# proiect.net
KiCad netlist of a schematic drawn in EAGLE
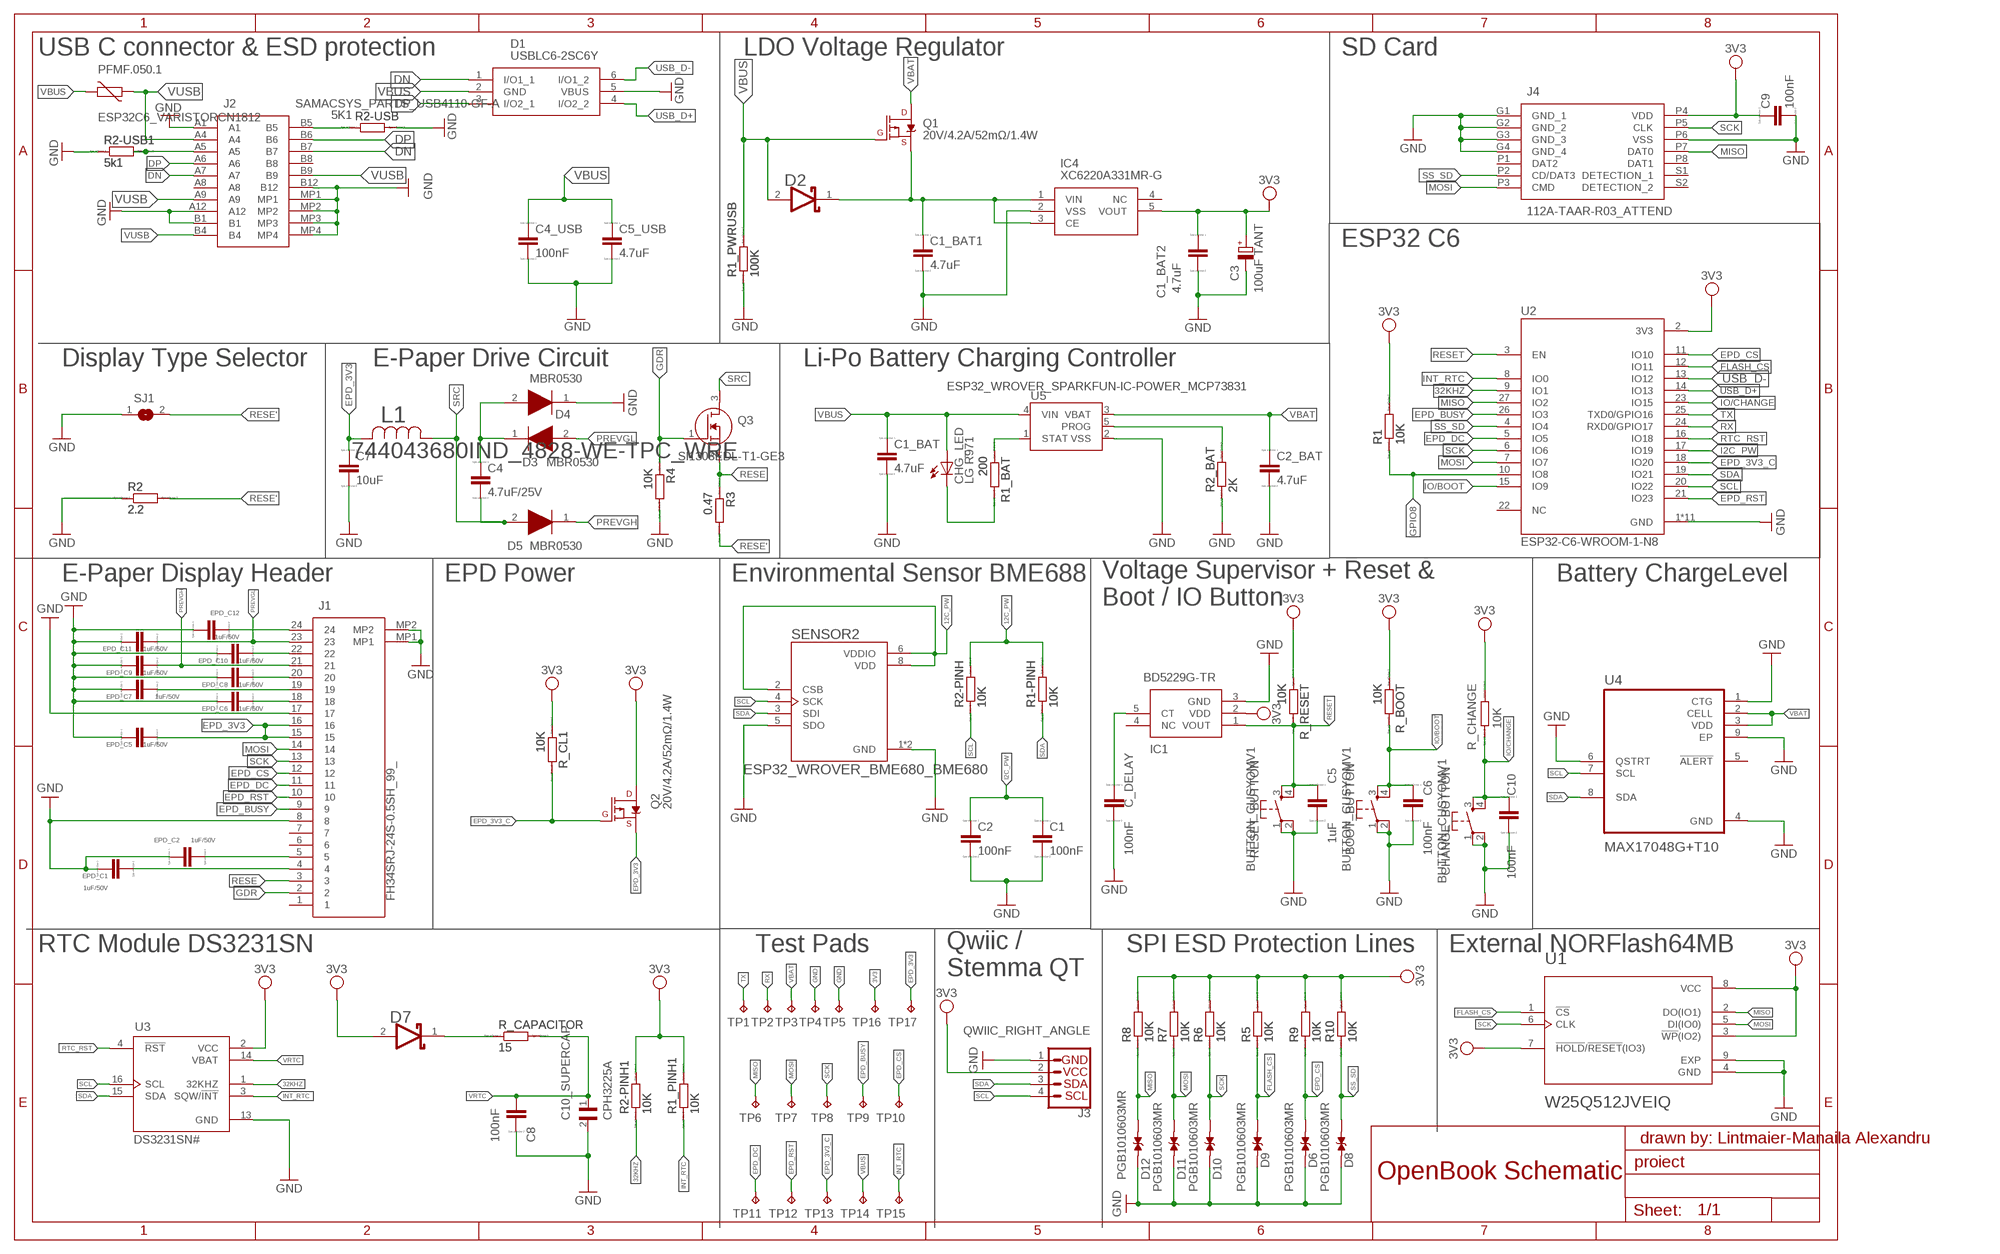
[diagram p0: schematic, sheet 1]

(export (version "E")
  (design (tool "Eeschema 10.0.6"))
  (components
    (comp (ref "BOOT_BUTTON")
      (value "BUTTON_CUSYOMV1")
      (footprint "eagle-import:MYBUTTON")
      (libsource (lib "eagle-import") (part "BUTTON_CUSYOMV1"))
    )
    (comp (ref "C1")
      (value "100nF")
      (footprint "eagle-import:EAGLE-LTSPICE_C0402")
      (libsource (lib "eagle-import") (part "EAGLE-LTSPICE_CC0402"))
    )
    (comp (ref "C1_BAT")
      (value "4.7uF")
      (footprint "eagle-import:EAGLE-LTSPICE_C0402")
      (libsource (lib "eagle-import") (part "EAGLE-LTSPICE_CC0402"))
    )
    (comp (ref "C1_BAT1")
      (value "4.7uF")
      (footprint "eagle-import:EAGLE-LTSPICE_C0402")
      (libsource (lib "eagle-import") (part "EAGLE-LTSPICE_CC0402"))
    )
    (comp (ref "C1_BAT2")
      (value "4.7uF")
      (footprint "eagle-import:EAGLE-LTSPICE_C0402")
      (libsource (lib "eagle-import") (part "EAGLE-LTSPICE_CC0402"))
    )
    (comp (ref "C2")
      (value "100nF")
      (footprint "eagle-import:EAGLE-LTSPICE_C0402")
      (libsource (lib "eagle-import") (part "EAGLE-LTSPICE_CC0402"))
    )
    (comp (ref "C2_BAT")
      (value "4.7uF")
      (footprint "eagle-import:EAGLE-LTSPICE_C0402")
      (libsource (lib "eagle-import") (part "EAGLE-LTSPICE_CC0402"))
    )
    (comp (ref "C3")
      (value "100uF TANT")
      (footprint "eagle-import:RCL_CT3528")
      (libsource (lib "eagle-import") (part "RCL_CPOL-EUCT3528"))
    )
    (comp (ref "C4")
      (value "4.7uF/25V")
      (footprint "eagle-import:EAGLE-LTSPICE_C0402")
      (libsource (lib "eagle-import") (part "EAGLE-LTSPICE_CC0402"))
    )
    (comp (ref "C4_USB")
      (value "100nF")
      (footprint "eagle-import:EAGLE-LTSPICE_C0402")
      (libsource (lib "eagle-import") (part "EAGLE-LTSPICE_CC0402"))
    )
    (comp (ref "C5")
      (value "1uF")
      (footprint "eagle-import:EAGLE-LTSPICE_C0402")
      (libsource (lib "eagle-import") (part "EAGLE-LTSPICE_CC0402"))
    )
    (comp (ref "C5_USB")
      (value "4.7uF")
      (footprint "eagle-import:EAGLE-LTSPICE_C0402")
      (libsource (lib "eagle-import") (part "EAGLE-LTSPICE_CC0402"))
    )
    (comp (ref "C6")
      (value "100nF")
      (footprint "eagle-import:EAGLE-LTSPICE_C0402")
      (libsource (lib "eagle-import") (part "EAGLE-LTSPICE_CC0402"))
    )
    (comp (ref "C7")
      (value "10uF")
      (footprint "eagle-import:EAGLE-LTSPICE_C0402")
      (libsource (lib "eagle-import") (part "EAGLE-LTSPICE_CC0402"))
    )
    (comp (ref "C8")
      (value "100nF")
      (footprint "eagle-import:EAGLE-LTSPICE_C0402")
      (libsource (lib "eagle-import") (part "EAGLE-LTSPICE_CC0402"))
    )
    (comp (ref "C9")
      (value "100nF")
      (footprint "eagle-import:EAGLE-LTSPICE_C0402")
      (libsource (lib "eagle-import") (part "EAGLE-LTSPICE_CC0402"))
    )
    (comp (ref "C10")
      (value "100nF")
      (footprint "eagle-import:EAGLE-LTSPICE_C0402")
      (libsource (lib "eagle-import") (part "EAGLE-LTSPICE_CC0402"))
    )
    (comp (ref "C10_SUPERCAP")
      (value "CPH3225A")
      (footprint "eagle-import:CAPCP3225X100N")
      (fields (field (name "MF") "Seiko Instruments"))
      (libsource (lib "eagle-import") (part "CPH3225A"))
    )
    (comp (ref "CHANGE_BUTTON")
      (value "BUTTON_CUSYOMV1")
      (footprint "eagle-import:MYBUTTON")
      (libsource (lib "eagle-import") (part "BUTTON_CUSYOMV1"))
    )
    (comp (ref "CHG_LED")
      (value "LG R971")
      (footprint "eagle-import:ADAFRUIT_CHIP-LED0603")
      (libsource (lib "eagle-import") (part "ADAFRUIT_LEDCHIP-LED0603"))
    )
    (comp (ref "C_DELAY")
      (value "100nF")
      (footprint "eagle-import:EAGLE-LTSPICE_C0402")
      (libsource (lib "eagle-import") (part "EAGLE-LTSPICE_CC0402"))
    )
    (comp (ref "D1")
      (value "USBLC6-2SC6Y")
      (footprint "eagle-import:SOT95P280X145-6N")
      (fields (field (name "MF") "STMicroelectronics"))
      (libsource (lib "eagle-import") (part "USBLC6-2SC6Y"))
    )
    (comp (ref "D2")
      (value "ESP32_WROVER_AVX---SD0805S020S1R0_AVX_SD0805S020S1R0_0_0AVX_SD0805S020S1R0_0_0")
      (footprint "eagle-import:ESP32_WROVER_AVX---SD0805S020S1R0_AVX_SD0805S020S1R0_0")
      (fields
        (field (name "DIGIKEY_PART_NUMBER") "478-7800-1-ND")
        (field (name "MF") "AVX")
        (field (name "MOUSER_PART_NUMBER") "581-SD0805S020S1R0")
      )
      (libsource (lib "eagle-import") (part "ESP32_WROVER_AVX---SD0805S020S1R0_AVX_SD0805S020S1R0_0_0AVX_SD0805S020S1R0_0_0"))
    )
    (comp (ref "D3")
      (value "MBR0530")
      (footprint "eagle-import:SOD3716X135N")
      (fields (field (name "MF") "ON Semiconductor"))
      (libsource (lib "eagle-import") (part "MBR0530"))
    )
    (comp (ref "D4")
      (value "MBR0530")
      (footprint "eagle-import:SOD3716X135N")
      (fields (field (name "MF") "ON Semiconductor"))
      (libsource (lib "eagle-import") (part "MBR0530"))
    )
    (comp (ref "D5")
      (value "MBR0530")
      (footprint "eagle-import:SOD3716X135N")
      (fields (field (name "MF") "ON Semiconductor"))
      (libsource (lib "eagle-import") (part "MBR0530"))
    )
    (comp (ref "D6")
      (value "PGB1010603MR")
      (footprint "eagle-import:DIOC1608X36N")
      (fields (field (name "MF") "Littelfuse Inc."))
      (libsource (lib "eagle-import") (part "PGB1010603MR"))
    )
    (comp (ref "D7")
      (value "ESP32_WROVER_AVX---SD0805S020S1R0_AVX_SD0805S020S1R0_0_0AVX_SD0805S020S1R0_0_0")
      (footprint "eagle-import:ESP32_WROVER_AVX---SD0805S020S1R0_AVX_SD0805S020S1R0_0")
      (fields
        (field (name "DIGIKEY_PART_NUMBER") "478-7800-1-ND")
        (field (name "MF") "AVX")
        (field (name "MOUSER_PART_NUMBER") "581-SD0805S020S1R0")
      )
      (libsource (lib "eagle-import") (part "ESP32_WROVER_AVX---SD0805S020S1R0_AVX_SD0805S020S1R0_0_0AVX_SD0805S020S1R0_0_0"))
    )
    (comp (ref "D8")
      (value "PGB1010603MR")
      (footprint "eagle-import:DIOC1608X36N")
      (fields (field (name "MF") "Littelfuse Inc."))
      (libsource (lib "eagle-import") (part "PGB1010603MR"))
    )
    (comp (ref "D9")
      (value "PGB1010603MR")
      (footprint "eagle-import:DIOC1608X36N")
      (fields (field (name "MF") "Littelfuse Inc."))
      (libsource (lib "eagle-import") (part "PGB1010603MR"))
    )
    (comp (ref "D10")
      (value "PGB1010603MR")
      (footprint "eagle-import:DIOC1608X36N")
      (fields (field (name "MF") "Littelfuse Inc."))
      (libsource (lib "eagle-import") (part "PGB1010603MR"))
    )
    (comp (ref "D11")
      (value "PGB1010603MR")
      (footprint "eagle-import:DIOC1608X36N")
      (fields (field (name "MF") "Littelfuse Inc."))
      (libsource (lib "eagle-import") (part "PGB1010603MR"))
    )
    (comp (ref "D12")
      (value "PGB1010603MR")
      (footprint "eagle-import:DIOC1608X36N")
      (fields (field (name "MF") "Littelfuse Inc."))
      (libsource (lib "eagle-import") (part "PGB1010603MR"))
    )
    (comp (ref "EPD_C1")
      (value "1uF/50V")
      (footprint "eagle-import:EAGLE-LTSPICE_C0402")
      (libsource (lib "eagle-import") (part "EAGLE-LTSPICE_CC0402"))
    )
    (comp (ref "EPD_C2")
      (value "1uF/50V")
      (footprint "eagle-import:EAGLE-LTSPICE_C0402")
      (libsource (lib "eagle-import") (part "EAGLE-LTSPICE_CC0402"))
    )
    (comp (ref "EPD_C5")
      (value "1uF/50V")
      (footprint "eagle-import:EAGLE-LTSPICE_C0402")
      (libsource (lib "eagle-import") (part "EAGLE-LTSPICE_CC0402"))
    )
    (comp (ref "EPD_C6")
      (value "1uF/50V")
      (footprint "eagle-import:EAGLE-LTSPICE_C0402")
      (libsource (lib "eagle-import") (part "EAGLE-LTSPICE_CC0402"))
    )
    (comp (ref "EPD_C7")
      (value "1uF/50V")
      (footprint "eagle-import:EAGLE-LTSPICE_C0402")
      (libsource (lib "eagle-import") (part "EAGLE-LTSPICE_CC0402"))
    )
    (comp (ref "EPD_C8")
      (value "1uF/50V")
      (footprint "eagle-import:EAGLE-LTSPICE_C0402")
      (libsource (lib "eagle-import") (part "EAGLE-LTSPICE_CC0402"))
    )
    (comp (ref "EPD_C9")
      (value "1uF/50V")
      (footprint "eagle-import:EAGLE-LTSPICE_C0402")
      (libsource (lib "eagle-import") (part "EAGLE-LTSPICE_CC0402"))
    )
    (comp (ref "EPD_C10")
      (value "1uF/50V")
      (footprint "eagle-import:EAGLE-LTSPICE_C0402")
      (libsource (lib "eagle-import") (part "EAGLE-LTSPICE_CC0402"))
    )
    (comp (ref "EPD_C11")
      (value "1uF/50V")
      (footprint "eagle-import:EAGLE-LTSPICE_C0402")
      (libsource (lib "eagle-import") (part "EAGLE-LTSPICE_CC0402"))
    )
    (comp (ref "EPD_C12")
      (value "1uF/50V")
      (footprint "eagle-import:EAGLE-LTSPICE_C0402")
      (libsource (lib "eagle-import") (part "EAGLE-LTSPICE_CC0402"))
    )
    (comp (ref "IC1")
      (value "BD5229G-TR")
      (footprint "eagle-import:SOT95P280X125-5N")
      (fields (field (name "MOUSER_PART_NUMBER") "755-BD5229G-TR"))
      (libsource (lib "eagle-import") (part "BD5229G-TR"))
    )
    (comp (ref "IC4")
      (value "XC6220A331MR-G")
      (footprint "eagle-import:SOT95P280X120-5N")
      (fields (field (name "MOUSER_PART_NUMBER") "865-XC6220A331MR-G"))
      (libsource (lib "eagle-import") (part "XC6220A331MR-G"))
    )
    (comp (ref "J1")
      (value "FH34SRJ-24S-0.5SH_99_")
      (footprint "eagle-import:FH34SRJ24S05SH99")
      (fields
        (field (name "MANUFACTURER_PART_NUMBER") "FH34SRJ-24S-0.5SH(99)")
        (field (name "MOUSER_PART_NUMBER") "798-FH34SRJ24S05SH99")
      )
      (libsource (lib "eagle-import") (part "FH34SRJ-24S-0.5SH_99_"))
    )
    (comp (ref "J2")
      (value "SAMACSYS_PARTS_USB4110-GF-A")
      (footprint "eagle-import:SAMACSYS_PARTS_USB4110GFA")
      (fields
        (field (name "MANUFACTURER_PART_NUMBER") "USB4110-GF-A")
        (field (name "MOUSER_PART_NUMBER") "640-USB4110-GF-A")
      )
      (libsource (lib "eagle-import") (part "SAMACSYS_PARTS_USB4110-GF-A"))
    )
    (comp (ref "J3")
      (value "QWIIC_RIGHT_ANGLE")
      (footprint "eagle-import:JST04_1MM_RA")
      (libsource (lib "eagle-import") (part "QWIIC_CONNECTORJS-1MM"))
    )
    (comp (ref "J4")
      (value "112A-TAAR-R03_ATTEND")
      (footprint "eagle-import:112ATAARR03ATTEND")
      (fields (field (name "MANUFACTURER_PART_NUMBER") "112A-TAAR-R03 ATTEND"))
      (libsource (lib "eagle-import") (part "112A-TAAR-R03_ATTEND"))
    )
    (comp (ref "L1")
      (value "744043680IND_4828-WE-TPC_WRE")
      (footprint "eagle-import:IND_4828-WE-TPC_WRE")
      (fields
        (field (name "MANUFACTURER_PART_NUMBER") "744043680")
        (field (name "COPYRIGHT") "Copyright (C) 2024 Ultra Librarian. All rights reserved.")
      )
      (libsource (lib "eagle-import") (part "744043680IND_4828-WE-TPC_WRE"))
    )
    (comp (ref "PFMF.050.1")
      (value "ESP32C6_VARISTORCN1812")
      (footprint "eagle-import:ESP32C6_VARISTOR_CT_CN1812")
      (libsource (lib "eagle-import") (part "ESP32C6_VARISTORCN1812"))
    )
    (comp (ref "Q1")
      (value "20V/4.2A/52mΩ/1.4W")
      (footprint "eagle-import:ESP32_WROVER_SPARKFUN-DISCRETESEMI_SOT23-3")
      (libsource (lib "eagle-import") (part "ESP32_WROVER_SPARKFUN-DISCRETESEMI_MOSFET_PCH-DMG2305UX-7"))
    )
    (comp (ref "Q2")
      (value "20V/4.2A/52mΩ/1.4W")
      (footprint "eagle-import:ESP32_WROVER_SPARKFUN-DISCRETESEMI_SOT23-3")
      (libsource (lib "eagle-import") (part "ESP32_WROVER_SPARKFUN-DISCRETESEMI_MOSFET_PCH-DMG2305UX-7"))
    )
    (comp (ref "Q3")
      (value "SI1308EDL-T1-GE3")
      (footprint "eagle-import:SOT65P210X110-3N")
      (fields (field (name "MF") "Vishay Siliconix"))
      (libsource (lib "eagle-import") (part "SI1308EDL-T1-GE3"))
    )
    (comp (ref "R1")
      (value "10K")
      (footprint "eagle-import:ESP32_WROVER_EAGLE-LTSPICE_R0402")
      (libsource (lib "eagle-import") (part "ESP32_WROVER_EAGLE-LTSPICE_RR0402"))
    )
    (comp (ref "R1-PINH")
      (value "10K")
      (footprint "eagle-import:ESP32_WROVER_EAGLE-LTSPICE_R0402")
      (libsource (lib "eagle-import") (part "ESP32_WROVER_EAGLE-LTSPICE_RR0402"))
    )
    (comp (ref "R1_BAT")
      (value "200")
      (footprint "eagle-import:ESP32_WROVER_EAGLE-LTSPICE_R0402")
      (libsource (lib "eagle-import") (part "ESP32_WROVER_EAGLE-LTSPICE_RR0402"))
    )
    (comp (ref "R1_PINH1")
      (value "10K")
      (footprint "eagle-import:ESP32_WROVER_EAGLE-LTSPICE_R0402")
      (libsource (lib "eagle-import") (part "ESP32_WROVER_EAGLE-LTSPICE_RR0402"))
    )
    (comp (ref "R1_PWRUSB")
      (value "100K")
      (footprint "eagle-import:ESP32_WROVER_EAGLE-LTSPICE_R0402")
      (libsource (lib "eagle-import") (part "ESP32_WROVER_EAGLE-LTSPICE_RR0402"))
    )
    (comp (ref "R2")
      (value "2.2")
      (footprint "eagle-import:ESP32_WROVER_EAGLE-LTSPICE_R0402")
      (libsource (lib "eagle-import") (part "ESP32_WROVER_EAGLE-LTSPICE_RR0402"))
    )
    (comp (ref "R2-PINH")
      (value "10K")
      (footprint "eagle-import:ESP32_WROVER_EAGLE-LTSPICE_R0402")
      (libsource (lib "eagle-import") (part "ESP32_WROVER_EAGLE-LTSPICE_RR0402"))
    )
    (comp (ref "R2-PINH1")
      (value "10K")
      (footprint "eagle-import:ESP32_WROVER_EAGLE-LTSPICE_R0402")
      (libsource (lib "eagle-import") (part "ESP32_WROVER_EAGLE-LTSPICE_RR0402"))
    )
    (comp (ref "R2-USB")
      (value "5K1")
      (footprint "eagle-import:ESP32_WROVER_EAGLE-LTSPICE_R0402")
      (libsource (lib "eagle-import") (part "ESP32_WROVER_EAGLE-LTSPICE_RR0402"))
    )
    (comp (ref "R2-USB1")
      (value "5k1")
      (footprint "eagle-import:ESP32_WROVER_EAGLE-LTSPICE_R0402")
      (libsource (lib "eagle-import") (part "ESP32_WROVER_EAGLE-LTSPICE_RR0402"))
    )
    (comp (ref "R2_BAT")
      (value "2K")
      (footprint "eagle-import:ESP32_WROVER_EAGLE-LTSPICE_R0402")
      (libsource (lib "eagle-import") (part "ESP32_WROVER_EAGLE-LTSPICE_RR0402"))
    )
    (comp (ref "R3")
      (value "0.47")
      (footprint "eagle-import:ESP32_WROVER_EAGLE-LTSPICE_R0402")
      (libsource (lib "eagle-import") (part "ESP32_WROVER_EAGLE-LTSPICE_RR0402"))
    )
    (comp (ref "R4")
      (value "10K")
      (footprint "eagle-import:ESP32_WROVER_EAGLE-LTSPICE_R0402")
      (libsource (lib "eagle-import") (part "ESP32_WROVER_EAGLE-LTSPICE_RR0402"))
    )
    (comp (ref "R5")
      (value "10K")
      (footprint "eagle-import:ESP32_WROVER_EAGLE-LTSPICE_R0402")
      (libsource (lib "eagle-import") (part "ESP32_WROVER_EAGLE-LTSPICE_RR0402"))
    )
    (comp (ref "R6")
      (value "10K")
      (footprint "eagle-import:ESP32_WROVER_EAGLE-LTSPICE_R0402")
      (libsource (lib "eagle-import") (part "ESP32_WROVER_EAGLE-LTSPICE_RR0402"))
    )
    (comp (ref "R7")
      (value "10K")
      (footprint "eagle-import:ESP32_WROVER_EAGLE-LTSPICE_R0402")
      (libsource (lib "eagle-import") (part "ESP32_WROVER_EAGLE-LTSPICE_RR0402"))
    )
    (comp (ref "R8")
      (value "10K")
      (footprint "eagle-import:ESP32_WROVER_EAGLE-LTSPICE_R0402")
      (libsource (lib "eagle-import") (part "ESP32_WROVER_EAGLE-LTSPICE_RR0402"))
    )
    (comp (ref "R9")
      (value "10K")
      (footprint "eagle-import:ESP32_WROVER_EAGLE-LTSPICE_R0402")
      (libsource (lib "eagle-import") (part "ESP32_WROVER_EAGLE-LTSPICE_RR0402"))
    )
    (comp (ref "R10")
      (value "10K")
      (footprint "eagle-import:ESP32_WROVER_EAGLE-LTSPICE_R0402")
      (libsource (lib "eagle-import") (part "ESP32_WROVER_EAGLE-LTSPICE_RR0402"))
    )
    (comp (ref "RESET_BUTTON")
      (value "BUTTON_CUSYOMV1")
      (footprint "eagle-import:MYBUTTON")
      (libsource (lib "eagle-import") (part "BUTTON_CUSYOMV1"))
    )
    (comp (ref "R_BOOT")
      (value "10K")
      (footprint "eagle-import:ESP32_WROVER_EAGLE-LTSPICE_R0402")
      (libsource (lib "eagle-import") (part "ESP32_WROVER_EAGLE-LTSPICE_RR0402"))
    )
    (comp (ref "R_CAPACITOR")
      (value "15")
      (footprint "eagle-import:ESP32_WROVER_EAGLE-LTSPICE_R0402")
      (libsource (lib "eagle-import") (part "ESP32_WROVER_EAGLE-LTSPICE_RR0402"))
    )
    (comp (ref "R_CHANGE")
      (value "10K")
      (footprint "eagle-import:ESP32_WROVER_EAGLE-LTSPICE_R0402")
      (libsource (lib "eagle-import") (part "ESP32_WROVER_EAGLE-LTSPICE_RR0402"))
    )
    (comp (ref "R_CL1")
      (value "10K")
      (footprint "eagle-import:ESP32_WROVER_EAGLE-LTSPICE_R0402")
      (libsource (lib "eagle-import") (part "ESP32_WROVER_EAGLE-LTSPICE_RR0402"))
    )
    (comp (ref "R_RESET")
      (value "10K")
      (footprint "eagle-import:ESP32_WROVER_EAGLE-LTSPICE_R0402")
      (libsource (lib "eagle-import") (part "ESP32_WROVER_EAGLE-LTSPICE_RR0402"))
    )
    (comp (ref "SENSOR2")
      (value "ESP32_WROVER_BME680_BME680")
      (footprint "eagle-import:ESP32_WROVER_BME680_PSON80P300X300X100-8N")
      (fields (field (name "MF") "Bosch Sensortec") (field (name "MP") "BME680"))
      (libsource (lib "eagle-import") (part "ESP32_WROVER_BME680_BME680"))
    )
    (comp (ref "SJ1") (value "SJ") (footprint "eagle-import:SJ") (libsource (lib "eagle-import") (part "SJ")))
    (comp (ref "TP1")
      (value "TPTP20R")
      (footprint "eagle-import:TP20R")
      (libsource (lib "eagle-import") (part "TPTP20R"))
    )
    (comp (ref "TP2")
      (value "TPTP20R")
      (footprint "eagle-import:TP20R")
      (libsource (lib "eagle-import") (part "TPTP20R"))
    )
    (comp (ref "TP3")
      (value "TPTP20R")
      (footprint "eagle-import:TP20R")
      (libsource (lib "eagle-import") (part "TPTP20R"))
    )
    (comp (ref "TP4")
      (value "TPTP20R")
      (footprint "eagle-import:TP20R")
      (libsource (lib "eagle-import") (part "TPTP20R"))
    )
    (comp (ref "TP5")
      (value "TPTP20R")
      (footprint "eagle-import:TP20R")
      (libsource (lib "eagle-import") (part "TPTP20R"))
    )
    (comp (ref "TP6")
      (value "TPTP20R")
      (footprint "eagle-import:TP20R")
      (libsource (lib "eagle-import") (part "TPTP20R"))
    )
    (comp (ref "TP7")
      (value "TPTP20R")
      (footprint "eagle-import:TP20R")
      (libsource (lib "eagle-import") (part "TPTP20R"))
    )
    (comp (ref "TP8")
      (value "TPTP20R")
      (footprint "eagle-import:TP20R")
      (libsource (lib "eagle-import") (part "TPTP20R"))
    )
    (comp (ref "TP9")
      (value "TPTP20R")
      (footprint "eagle-import:TP20R")
      (libsource (lib "eagle-import") (part "TPTP20R"))
    )
    (comp (ref "TP10")
      (value "TPTP20R")
      (footprint "eagle-import:TP20R")
      (libsource (lib "eagle-import") (part "TPTP20R"))
    )
    (comp (ref "TP11")
      (value "TPTP20R")
      (footprint "eagle-import:TP20R")
      (libsource (lib "eagle-import") (part "TPTP20R"))
    )
    (comp (ref "TP12")
      (value "TPTP20R")
      (footprint "eagle-import:TP20R")
      (libsource (lib "eagle-import") (part "TPTP20R"))
    )
    (comp (ref "TP13")
      (value "TPTP20R")
      (footprint "eagle-import:TP20R")
      (libsource (lib "eagle-import") (part "TPTP20R"))
    )
    (comp (ref "TP14")
      (value "TPTP20R")
      (footprint "eagle-import:TP20R")
      (libsource (lib "eagle-import") (part "TPTP20R"))
    )
    (comp (ref "TP15")
      (value "TPTP20R")
      (footprint "eagle-import:TP20R")
      (libsource (lib "eagle-import") (part "TPTP20R"))
    )
    (comp (ref "TP16")
      (value "TPTP20R")
      (footprint "eagle-import:TP20R")
      (libsource (lib "eagle-import") (part "TPTP20R"))
    )
    (comp (ref "TP17")
      (value "TPTP20R")
      (footprint "eagle-import:TP20R")
      (libsource (lib "eagle-import") (part "TPTP20R"))
    )
    (comp (ref "U1")
      (value "W25Q512JVEIQ")
      (footprint "eagle-import:SON127P600X800X80-9N")
      (fields (field (name "MF") "Winbond Electronics"))
      (libsource (lib "eagle-import") (part "W25Q512JVEIQ"))
    )
    (comp (ref "U2")
      (value "ESP32-C6-WROOM-1-N8")
      (footprint "eagle-import:XCVR_ESP32-C6-WROOM-1-N8")
      (fields (field (name "MF") "Espressif Systems"))
      (libsource (lib "eagle-import") (part "ESP32-C6-WROOM-1-N8"))
    )
    (comp (ref "U3")
      (value "DS3231SN#")
      (footprint "eagle-import:SOIC127P1032X265-16N")
      (fields (field (name "MF") "Analog Devices"))
      (libsource (lib "eagle-import") (part "DS3231SN#"))
    )
    (comp (ref "U4")
      (value "MAX17048G+T10")
      (footprint "eagle-import:SON50P200X200X80-9N")
      (fields (field (name "MF") "Analog Devices"))
      (libsource (lib "eagle-import") (part "MAX17048G+T10"))
    )
    (comp (ref "U5")
      (value "ESP32_WROVER_SPARKFUN-IC-POWER_MCP73831")
      (footprint "eagle-import:ESP32_WROVER_SPARKFUN-IC-POWER_SOT23-5")
      (libsource (lib "eagle-import") (part "ESP32_WROVER_SPARKFUN-IC-POWER_MCP73831"))
    )
  )
  (nets
    (net (code "1") (name "3V3") (class "Default")
      (node (ref "C1_BAT2") (pin "1") (pinfunction "1_1") (pintype "passive"))
      (node (ref "C3") (pin "+") (pinfunction "+_+") (pintype "passive"))
      (node (ref "C9") (pin "1") (pinfunction "1_1") (pintype "passive"))
      (node (ref "D7") (pin "2") (pinfunction "ANODE_2") (pintype "bidirectional"))
      (node (ref "IC1") (pin "2") (pinfunction "VDD_2") (pintype "bidirectional"))
      (node (ref "IC4") (pin "5") (pinfunction "VOUT_5") (pintype "bidirectional"))
      (node (ref "J3") (pin "2") (pinfunction "2_2") (pintype "power_in"))
      (node (ref "J4") (pin "P4") (pinfunction "VDD_P4") (pintype "bidirectional"))
      (node (ref "Q2") (pin "3") (pinfunction "D_3") (pintype "bidirectional"))
      (node (ref "R1") (pin "2") (pinfunction "2_2") (pintype "passive"))
      (node (ref "R10") (pin "2") (pinfunction "2_2") (pintype "passive"))
      (node (ref "R1_PINH1") (pin "2") (pinfunction "2_2") (pintype "passive"))
      (node (ref "R2-PINH1") (pin "2") (pinfunction "2_2") (pintype "passive"))
      (node (ref "R5") (pin "2") (pinfunction "2_2") (pintype "passive"))
      (node (ref "R6") (pin "2") (pinfunction "2_2") (pintype "passive"))
      (node (ref "R7") (pin "2") (pinfunction "2_2") (pintype "passive"))
      (node (ref "R8") (pin "2") (pinfunction "2_2") (pintype "passive"))
      (node (ref "R9") (pin "2") (pinfunction "2_2") (pintype "passive"))
      (node (ref "R_BOOT") (pin "1") (pinfunction "1_1") (pintype "passive"))
      (node (ref "R_CHANGE") (pin "1") (pinfunction "1_1") (pintype "passive"))
      (node (ref "R_CL1") (pin "1") (pinfunction "1_1") (pintype "passive"))
      (node (ref "R_RESET") (pin "1") (pinfunction "1_1") (pintype "passive"))
      (node (ref "TP16") (pin "TP") (pinfunction "TP_TP") (pintype "input"))
      (node (ref "U1") (pin "3") (pinfunction "~{WP}(IO2)_3") (pintype "bidirectional"))
      (node (ref "U1") (pin "7") (pinfunction "~{HOLD}/~{RESET}(IO3)_7") (pintype "bidirectional"))
      (node (ref "U1") (pin "8") (pinfunction "VCC_8") (pintype "power_in"))
      (node (ref "U2") (pin "2") (pinfunction "3V3_2") (pintype "power_in"))
      (node (ref "U3") (pin "2") (pinfunction "VCC_2") (pintype "power_in"))
    )
    (net (code "2") (name "12C_PW") (class "Default")
      (node (ref "R1-PINH") (pin "2") (pinfunction "2_2") (pintype "passive"))
      (node (ref "R2-PINH") (pin "2") (pinfunction "2_2") (pintype "passive"))
      (node (ref "SENSOR2") (pin "2") (pinfunction "CSB_2") (pintype "input"))
      (node (ref "SENSOR2") (pin "6") (pinfunction "VDDIO_6") (pintype "power_in"))
      (node (ref "SENSOR2") (pin "8") (pinfunction "VDD_8") (pintype "power_in"))
    )
    (net (code "3") (name "32KHZ") (class "Default")
      (node (ref "R2-PINH1") (pin "1") (pinfunction "1_1") (pintype "passive"))
      (node (ref "U2") (pin "9") (pinfunction "IO1_9") (pintype "bidirectional"))
      (node (ref "U3") (pin "1") (pinfunction "32KHZ_1") (pintype "output"))
    )
    (net (code "4") (name "DN") (class "Default")
      (node (ref "D1") (pin "1") (pinfunction "I/O1_1_1") (pintype "bidirectional"))
      (node (ref "J2") (pin "A7") (pinfunction "A7_A7") (pintype "bidirectional"))
      (node (ref "J2") (pin "B7") (pinfunction "B7_B7") (pintype "bidirectional"))
    )
    (net (code "5") (name "DP") (class "Default")
      (node (ref "D1") (pin "3") (pinfunction "I/O2_1_3") (pintype "bidirectional"))
      (node (ref "J2") (pin "A6") (pinfunction "A6_A6") (pintype "bidirectional"))
      (node (ref "J2") (pin "B6") (pinfunction "B6_B6") (pintype "bidirectional"))
    )
    (net (code "6") (name "EPD_3V3") (class "Default")
      (node (ref "C7") (pin "1") (pinfunction "1_1") (pintype "passive"))
      (node (ref "EPD_C5") (pin "2") (pinfunction "2_2") (pintype "passive"))
      (node (ref "J1") (pin "15") (pinfunction "15_15") (pintype "bidirectional"))
      (node (ref "J1") (pin "16") (pinfunction "16_16") (pintype "bidirectional"))
      (node (ref "L1") (pin "2") (pinfunction "2_2") (pintype "passive"))
      (node (ref "Q2") (pin "2") (pinfunction "S_2") (pintype "bidirectional"))
      (node (ref "TP17") (pin "TP") (pinfunction "TP_TP") (pintype "input"))
    )
    (net (code "7") (name "EPD_3V3_C") (class "Default")
      (node (ref "Q2") (pin "1") (pinfunction "G_1") (pintype "bidirectional"))
      (node (ref "R_CL1") (pin "2") (pinfunction "2_2") (pintype "passive"))
      (node (ref "TP13") (pin "TP") (pinfunction "TP_TP") (pintype "input"))
      (node (ref "U2") (pin "18") (pinfunction "IO20_18") (pintype "bidirectional"))
    )
    (net (code "8") (name "EPD_BUSY") (class "Default")
      (node (ref "J1") (pin "9") (pinfunction "9_9") (pintype "bidirectional"))
      (node (ref "TP9") (pin "TP") (pinfunction "TP_TP") (pintype "input"))
      (node (ref "U2") (pin "26") (pinfunction "IO3_26") (pintype "bidirectional"))
    )
    (net (code "9") (name "EPD_CS") (class "Default")
      (node (ref "D6") (pin "2") (pinfunction "2_2") (pintype "passive"))
      (node (ref "J1") (pin "12") (pinfunction "12_12") (pintype "bidirectional"))
      (node (ref "R9") (pin "1") (pinfunction "1_1") (pintype "passive"))
      (node (ref "TP10") (pin "TP") (pinfunction "TP_TP") (pintype "input"))
      (node (ref "U2") (pin "11") (pinfunction "IO10_11") (pintype "bidirectional"))
    )
    (net (code "10") (name "EPD_DC") (class "Default")
      (node (ref "J1") (pin "11") (pinfunction "11_11") (pintype "bidirectional"))
      (node (ref "TP11") (pin "TP") (pinfunction "TP_TP") (pintype "input"))
      (node (ref "U2") (pin "5") (pinfunction "IO5_5") (pintype "bidirectional"))
    )
    (net (code "11") (name "EPD_RST") (class "Default")
      (node (ref "J1") (pin "10") (pinfunction "10_10") (pintype "bidirectional"))
      (node (ref "TP12") (pin "TP") (pinfunction "TP_TP") (pintype "input"))
      (node (ref "U2") (pin "21") (pinfunction "IO23_21") (pintype "bidirectional"))
    )
    (net (code "12") (name "FLASH_CS") (class "Default")
      (node (ref "D9") (pin "2") (pinfunction "2_2") (pintype "passive"))
      (node (ref "R5") (pin "1") (pinfunction "1_1") (pintype "passive"))
      (node (ref "U1") (pin "1") (pinfunction "~{CS}_1") (pintype "input"))
      (node (ref "U2") (pin "12") (pinfunction "IO11_12") (pintype "bidirectional"))
    )
    (net (code "13") (name "GDR") (class "Default")
      (node (ref "J1") (pin "2") (pinfunction "2_2") (pintype "bidirectional"))
      (node (ref "Q3") (pin "1") (pinfunction "G_1") (pintype "bidirectional"))
      (node (ref "R4") (pin "1") (pinfunction "1_1") (pintype "passive"))
    )
    (net (code "14") (name "GND") (class "Default")
      (node (ref "BOOT_BUTTON") (pin "1") (pinfunction "1_1") (pintype "passive"))
      (node (ref "BOOT_BUTTON") (pin "2") (pinfunction "2_2") (pintype "passive"))
      (node (ref "C1") (pin "2") (pinfunction "2_2") (pintype "passive"))
      (node (ref "C10") (pin "2") (pinfunction "2_2") (pintype "passive"))
      (node (ref "C10_SUPERCAP") (pin "2") (pinfunction "2_2") (pintype "passive"))
      (node (ref "C1_BAT") (pin "2") (pinfunction "2_2") (pintype "passive"))
      (node (ref "C1_BAT1") (pin "2") (pinfunction "2_2") (pintype "passive"))
      (node (ref "C1_BAT2") (pin "2") (pinfunction "2_2") (pintype "passive"))
      (node (ref "C2") (pin "2") (pinfunction "2_2") (pintype "passive"))
      (node (ref "C2_BAT") (pin "2") (pinfunction "2_2") (pintype "passive"))
      (node (ref "C3") (pin "-") (pinfunction "-_-") (pintype "passive"))
      (node (ref "C4_USB") (pin "2") (pinfunction "2_2") (pintype "passive"))
      (node (ref "C5") (pin "2") (pinfunction "2_2") (pintype "passive"))
      (node (ref "C5_USB") (pin "2") (pinfunction "2_2") (pintype "passive"))
      (node (ref "C6") (pin "2") (pinfunction "2_2") (pintype "passive"))
      (node (ref "C7") (pin "2") (pinfunction "2_2") (pintype "passive"))
      (node (ref "C8") (pin "2") (pinfunction "2_2") (pintype "passive"))
      (node (ref "C9") (pin "2") (pinfunction "2_2") (pintype "passive"))
      (node (ref "CHANGE_BUTTON") (pin "1") (pinfunction "1_1") (pintype "passive"))
      (node (ref "CHANGE_BUTTON") (pin "2") (pinfunction "2_2") (pintype "passive"))
      (node (ref "C_DELAY") (pin "2") (pinfunction "2_2") (pintype "passive"))
      (node (ref "D1") (pin "5") (pinfunction "VBUS_5") (pintype "bidirectional"))
      (node (ref "D10") (pin "1") (pinfunction "1_1") (pintype "passive"))
      (node (ref "D11") (pin "1") (pinfunction "1_1") (pintype "passive"))
      (node (ref "D12") (pin "1") (pinfunction "1_1") (pintype "passive"))
      (node (ref "D4") (pin "1") (pinfunction "K_1") (pintype "bidirectional"))
      (node (ref "D6") (pin "1") (pinfunction "1_1") (pintype "passive"))
      (node (ref "D8") (pin "1") (pinfunction "1_1") (pintype "passive"))
      (node (ref "D9") (pin "1") (pinfunction "1_1") (pintype "passive"))
      (node (ref "EPD_C1") (pin "1") (pinfunction "1_1") (pintype "passive"))
      (node (ref "EPD_C10") (pin "1") (pinfunction "1_1") (pintype "passive"))
      (node (ref "EPD_C11") (pin "1") (pinfunction "1_1") (pintype "passive"))
      (node (ref "EPD_C12") (pin "1") (pinfunction "1_1") (pintype "passive"))
      (node (ref "EPD_C2") (pin "1") (pinfunction "1_1") (pintype "passive"))
      (node (ref "EPD_C5") (pin "1") (pinfunction "1_1") (pintype "passive"))
      (node (ref "EPD_C6") (pin "1") (pinfunction "1_1") (pintype "passive"))
      (node (ref "EPD_C7") (pin "1") (pinfunction "1_1") (pintype "passive"))
      (node (ref "EPD_C8") (pin "1") (pinfunction "1_1") (pintype "passive"))
      (node (ref "EPD_C9") (pin "1") (pinfunction "1_1") (pintype "passive"))
      (node (ref "IC1") (pin "3") (pinfunction "GND_3") (pintype "bidirectional"))
      (node (ref "IC4") (pin "2") (pinfunction "VSS_2") (pintype "bidirectional"))
      (node (ref "J1") (pin "17") (pinfunction "17_17") (pintype "bidirectional"))
      (node (ref "J1") (pin "8") (pinfunction "8_8") (pintype "bidirectional"))
      (node (ref "J1") (pin "MP1") (pinfunction "MP1_MP1") (pintype "bidirectional"))
      (node (ref "J1") (pin "MP2") (pinfunction "MP2_MP2") (pintype "bidirectional"))
      (node (ref "J2") (pin "A1") (pinfunction "A1_A1") (pintype "bidirectional"))
      (node (ref "J2") (pin "A12") (pinfunction "A12_A12") (pintype "bidirectional"))
      (node (ref "J2") (pin "B1") (pinfunction "B1_B1") (pintype "bidirectional"))
      (node (ref "J2") (pin "B12") (pinfunction "B12_B12") (pintype "bidirectional"))
      (node (ref "J2") (pin "MP1") (pinfunction "MP1_MP1") (pintype "bidirectional"))
      (node (ref "J2") (pin "MP2") (pinfunction "MP2_MP2") (pintype "bidirectional"))
      (node (ref "J2") (pin "MP3") (pinfunction "MP3_MP3") (pintype "bidirectional"))
      (node (ref "J2") (pin "MP4") (pinfunction "MP4_MP4") (pintype "bidirectional"))
      (node (ref "J3") (pin "1") (pinfunction "1_1") (pintype "power_in"))
      (node (ref "J4") (pin "G1") (pinfunction "GND_1_G1") (pintype "bidirectional"))
      (node (ref "J4") (pin "G2") (pinfunction "GND_2_G2") (pintype "bidirectional"))
      (node (ref "J4") (pin "G3") (pinfunction "GND_3_G3") (pintype "bidirectional"))
      (node (ref "J4") (pin "G4") (pinfunction "GND_4_G4") (pintype "bidirectional"))
      (node (ref "J4") (pin "P6") (pinfunction "VSS_P6") (pintype "bidirectional"))
      (node (ref "R1_PWRUSB") (pin "1") (pinfunction "1_1") (pintype "passive"))
      (node (ref "R2") (pin "1") (pinfunction "1_1") (pintype "passive"))
      (node (ref "R2-USB") (pin "2") (pinfunction "2_2") (pintype "passive"))
      (node (ref "R2-USB1") (pin "1") (pinfunction "1_1") (pintype "passive"))
      (node (ref "R2_BAT") (pin "1") (pinfunction "1_1") (pintype "passive"))
      (node (ref "R4") (pin "2") (pinfunction "2_2") (pintype "passive"))
      (node (ref "RESET_BUTTON") (pin "1") (pinfunction "1_1") (pintype "passive"))
      (node (ref "RESET_BUTTON") (pin "2") (pinfunction "2_2") (pintype "passive"))
      (node (ref "SENSOR2") (pin "1") (pinfunction "GND_1") (pintype "power_in"))
      (node (ref "SENSOR2") (pin "5") (pinfunction "SDO_5") (pintype "bidirectional"))
      (node (ref "SENSOR2") (pin "7") (pinfunction "GND_7") (pintype "power_in"))
      (node (ref "SJ1") (pin "1") (pinfunction "1_1") (pintype "passive"))
      (node (ref "TP4") (pin "TP") (pinfunction "TP_TP") (pintype "input"))
      (node (ref "TP5") (pin "TP") (pinfunction "TP_TP") (pintype "input"))
      (node (ref "U1") (pin "4") (pinfunction "GND_4") (pintype "power_in"))
      (node (ref "U1") (pin "9") (pinfunction "EXP_9") (pintype "passive"))
      (node (ref "U2") (pin "1") (pinfunction "GND_1") (pintype "power_in"))
      (node (ref "U2") (pin "28") (pinfunction "GND_28") (pintype "power_in"))
      (node (ref "U2") (pin "29_1") (pinfunction "GND_29_1") (pintype "power_in"))
      (node (ref "U2") (pin "29_2") (pinfunction "GND_29_2") (pintype "power_in"))
      (node (ref "U2") (pin "29_3") (pinfunction "GND_29_3") (pintype "power_in"))
      (node (ref "U2") (pin "29_4") (pinfunction "GND_29_4") (pintype "power_in"))
      (node (ref "U2") (pin "29_5") (pinfunction "GND_29_5") (pintype "power_in"))
      (node (ref "U2") (pin "29_6") (pinfunction "GND_29_6") (pintype "power_in"))
      (node (ref "U2") (pin "29_7") (pinfunction "GND_29_7") (pintype "power_in"))
      (node (ref "U2") (pin "29_8") (pinfunction "GND_29_8") (pintype "power_in"))
      (node (ref "U2") (pin "29_9") (pinfunction "GND_29_9") (pintype "power_in"))
      (node (ref "U3") (pin "13") (pinfunction "GND_13") (pintype "power_in"))
      (node (ref "U4") (pin "1") (pinfunction "CTG_1") (pintype "power_in"))
      (node (ref "U4") (pin "4") (pinfunction "GND_4") (pintype "power_in"))
      (node (ref "U4") (pin "6") (pinfunction "QSTRT_6") (pintype "input"))
      (node (ref "U4") (pin "9") (pinfunction "EP_9") (pintype "power_in"))
      (node (ref "U5") (pin "2") (pinfunction "VSS_2") (pintype "power_in"))
    )
    (net (code "15") (name "GPIO8") (class "Default")
      (node (ref "R1") (pin "1") (pinfunction "1_1") (pintype "passive"))
      (node (ref "U2") (pin "10") (pinfunction "IO8_10") (pintype "bidirectional"))
    )
    (net (code "16") (name "I2C_PW") (class "Default")
      (node (ref "C1") (pin "1") (pinfunction "1_1") (pintype "passive"))
      (node (ref "C2") (pin "1") (pinfunction "1_1") (pintype "passive"))
      (node (ref "U2") (pin "17") (pinfunction "IO19_17") (pintype "bidirectional"))
    )
    (net (code "17") (name "INT_RTC") (class "Default")
      (node (ref "R1_PINH1") (pin "1") (pinfunction "1_1") (pintype "passive"))
      (node (ref "TP15") (pin "TP") (pinfunction "TP_TP") (pintype "input"))
      (node (ref "U2") (pin "8") (pinfunction "IO0_8") (pintype "bidirectional"))
      (node (ref "U3") (pin "3") (pinfunction "SQW/~{INT}_3") (pintype "output"))
    )
    (net (code "18") (name "IO{slash}BOOT") (class "Default")
      (node (ref "BOOT_BUTTON") (pin "3") (pinfunction "3_3") (pintype "passive"))
      (node (ref "BOOT_BUTTON") (pin "4") (pinfunction "4_4") (pintype "passive"))
      (node (ref "C6") (pin "1") (pinfunction "1_1") (pintype "passive"))
      (node (ref "R_BOOT") (pin "2") (pinfunction "2_2") (pintype "passive"))
      (node (ref "U2") (pin "15") (pinfunction "IO9_15") (pintype "bidirectional"))
    )
    (net (code "19") (name "IO{slash}CHANGE") (class "Default")
      (node (ref "C10") (pin "1") (pinfunction "1_1") (pintype "passive"))
      (node (ref "CHANGE_BUTTON") (pin "3") (pinfunction "3_3") (pintype "passive"))
      (node (ref "CHANGE_BUTTON") (pin "4") (pinfunction "4_4") (pintype "passive"))
      (node (ref "R_CHANGE") (pin "2") (pinfunction "2_2") (pintype "passive"))
      (node (ref "U2") (pin "23") (pinfunction "IO15_23") (pintype "bidirectional"))
    )
    (net (code "20") (name "MISO") (class "Default")
      (node (ref "D12") (pin "2") (pinfunction "2_2") (pintype "passive"))
      (node (ref "J4") (pin "P7") (pinfunction "DAT0_P7") (pintype "bidirectional"))
      (node (ref "R8") (pin "1") (pinfunction "1_1") (pintype "passive"))
      (node (ref "TP6") (pin "TP") (pinfunction "TP_TP") (pintype "input"))
      (node (ref "U1") (pin "2") (pinfunction "DO(IO1)_2") (pintype "bidirectional"))
      (node (ref "U2") (pin "27") (pinfunction "IO2_27") (pintype "bidirectional"))
    )
    (net (code "21") (name "MOSI") (class "Default")
      (node (ref "D11") (pin "2") (pinfunction "2_2") (pintype "passive"))
      (node (ref "J1") (pin "14") (pinfunction "14_14") (pintype "bidirectional"))
      (node (ref "J4") (pin "P3") (pinfunction "CMD_P3") (pintype "bidirectional"))
      (node (ref "R7") (pin "1") (pinfunction "1_1") (pintype "passive"))
      (node (ref "TP7") (pin "TP") (pinfunction "TP_TP") (pintype "input"))
      (node (ref "U1") (pin "5") (pinfunction "DI(IO0)_5") (pintype "bidirectional"))
      (node (ref "U2") (pin "7") (pinfunction "IO7_7") (pintype "bidirectional"))
    )
    (net (code "22") (name "Net-(CHG_LED-PadC)") (class "Default")
      (node (ref "CHG_LED") (pin "C") (pinfunction "C_C") (pintype "passive"))
      (node (ref "R1_BAT") (pin "2") (pinfunction "2_2") (pintype "passive"))
    )
    (net (code "23") (name "Net-(D2-CATHODE)") (class "Default")
      (node (ref "C1_BAT1") (pin "1") (pinfunction "1_1") (pintype "passive"))
      (node (ref "D2") (pin "1") (pinfunction "CATHODE_1") (pintype "bidirectional"))
      (node (ref "IC4") (pin "1") (pinfunction "VIN_1") (pintype "bidirectional"))
      (node (ref "IC4") (pin "3") (pinfunction "CE_3") (pintype "bidirectional"))
      (node (ref "Q1") (pin "2") (pinfunction "S_2") (pintype "bidirectional"))
    )
    (net (code "24") (name "Net-(D3-K)") (class "Default")
      (node (ref "C4") (pin "1") (pinfunction "1_1") (pintype "passive"))
      (node (ref "D3") (pin "1") (pinfunction "K_1") (pintype "bidirectional"))
      (node (ref "D4") (pin "2") (pinfunction "A_2") (pintype "bidirectional"))
    )
    (net (code "25") (name "Net-(D7-CATHODE)") (class "Default")
      (node (ref "D7") (pin "1") (pinfunction "CATHODE_1") (pintype "bidirectional"))
      (node (ref "R_CAPACITOR") (pin "1") (pinfunction "1_1") (pintype "passive"))
    )
    (net (code "26") (name "Net-(EPD_C1-Pad2)") (class "Default")
      (node (ref "EPD_C1") (pin "2") (pinfunction "2_2") (pintype "passive"))
      (node (ref "J1") (pin "4") (pinfunction "4_4") (pintype "bidirectional"))
    )
    (net (code "27") (name "Net-(EPD_C2-Pad2)") (class "Default")
      (node (ref "EPD_C2") (pin "2") (pinfunction "2_2") (pintype "passive"))
      (node (ref "J1") (pin "5") (pinfunction "5_5") (pintype "bidirectional"))
    )
    (net (code "28") (name "Net-(EPD_C6-Pad2)") (class "Default")
      (node (ref "EPD_C6") (pin "2") (pinfunction "2_2") (pintype "passive"))
      (node (ref "J1") (pin "18") (pinfunction "18_18") (pintype "bidirectional"))
    )
    (net (code "29") (name "Net-(EPD_C7-Pad2)") (class "Default")
      (node (ref "EPD_C7") (pin "2") (pinfunction "2_2") (pintype "passive"))
      (node (ref "J1") (pin "19") (pinfunction "19_19") (pintype "bidirectional"))
    )
    (net (code "30") (name "Net-(EPD_C8-Pad2)") (class "Default")
      (node (ref "EPD_C8") (pin "2") (pinfunction "2_2") (pintype "passive"))
      (node (ref "J1") (pin "20") (pinfunction "20_20") (pintype "bidirectional"))
    )
    (net (code "31") (name "Net-(EPD_C10-Pad2)") (class "Default")
      (node (ref "EPD_C10") (pin "2") (pinfunction "2_2") (pintype "passive"))
      (node (ref "J1") (pin "22") (pinfunction "22_22") (pintype "bidirectional"))
    )
    (net (code "32") (name "Net-(EPD_C12-Pad2)") (class "Default")
      (node (ref "EPD_C12") (pin "2") (pinfunction "2_2") (pintype "passive"))
      (node (ref "J1") (pin "24") (pinfunction "24_24") (pintype "bidirectional"))
    )
    (net (code "33") (name "Net-(IC1-CT)") (class "Default")
      (node (ref "C_DELAY") (pin "1") (pinfunction "1_1") (pintype "passive"))
      (node (ref "IC1") (pin "5") (pinfunction "CT_5") (pintype "bidirectional"))
    )
    (net (code "34") (name "Net-(J2-PadA5)") (class "Default")
      (node (ref "J2") (pin "A5") (pinfunction "A5_A5") (pintype "bidirectional"))
      (node (ref "R2-USB1") (pin "2") (pinfunction "2_2") (pintype "passive"))
    )
    (net (code "35") (name "Net-(J2-PadB5)") (class "Default")
      (node (ref "J2") (pin "B5") (pinfunction "B5_B5") (pintype "bidirectional"))
      (node (ref "R2-USB") (pin "1") (pinfunction "1_1") (pintype "passive"))
    )
    (net (code "36") (name "Net-(U5-PROG)") (class "Default")
      (node (ref "R2_BAT") (pin "2") (pinfunction "2_2") (pintype "passive"))
      (node (ref "U5") (pin "5") (pinfunction "PROG_5") (pintype "input"))
    )
    (net (code "37") (name "Net-(U5-STAT)") (class "Default")
      (node (ref "R1_BAT") (pin "1") (pinfunction "1_1") (pintype "passive"))
      (node (ref "U5") (pin "1") (pinfunction "STAT_1") (pintype "output"))
    )
    (net (code "38") (name "PREVGH") (class "Default")
      (node (ref "D5") (pin "1") (pinfunction "K_1") (pintype "bidirectional"))
      (node (ref "EPD_C9") (pin "2") (pinfunction "2_2") (pintype "passive"))
      (node (ref "J1") (pin "21") (pinfunction "21_21") (pintype "bidirectional"))
    )
    (net (code "39") (name "PREVGL") (class "Default")
      (node (ref "D3") (pin "2") (pinfunction "A_2") (pintype "bidirectional"))
      (node (ref "EPD_C11") (pin "2") (pinfunction "2_2") (pintype "passive"))
      (node (ref "J1") (pin "23") (pinfunction "23_23") (pintype "bidirectional"))
    )
    (net (code "40") (name "RESE") (class "Default")
      (node (ref "J1") (pin "3") (pinfunction "3_3") (pintype "bidirectional"))
      (node (ref "Q3") (pin "2") (pinfunction "S_2") (pintype "bidirectional"))
      (node (ref "R3") (pin "1") (pinfunction "1_1") (pintype "passive"))
    )
    (net (code "41") (name "RESE'") (class "Default")
      (node (ref "R2") (pin "2") (pinfunction "2_2") (pintype "passive"))
      (node (ref "R3") (pin "2") (pinfunction "2_2") (pintype "passive"))
      (node (ref "SJ1") (pin "2") (pinfunction "2_2") (pintype "passive"))
    )
    (net (code "42") (name "RESET") (class "Default")
      (node (ref "C5") (pin "1") (pinfunction "1_1") (pintype "passive"))
      (node (ref "IC1") (pin "1") (pinfunction "VOUT_1") (pintype "bidirectional"))
      (node (ref "RESET_BUTTON") (pin "3") (pinfunction "3_3") (pintype "passive"))
      (node (ref "RESET_BUTTON") (pin "4") (pinfunction "4_4") (pintype "passive"))
      (node (ref "R_RESET") (pin "2") (pinfunction "2_2") (pintype "passive"))
      (node (ref "U2") (pin "3") (pinfunction "EN_3") (pintype "input"))
    )
    (net (code "43") (name "RTC_RST") (class "Default")
      (node (ref "U2") (pin "16") (pinfunction "IO18_16") (pintype "bidirectional"))
      (node (ref "U3") (pin "4") (pinfunction "~{RST}_4") (pintype "input"))
    )
    (net (code "44") (name "RX") (class "Default")
      (node (ref "TP2") (pin "TP") (pinfunction "TP_TP") (pintype "input"))
      (node (ref "U2") (pin "24") (pinfunction "RXD0/GPIO17_24") (pintype "bidirectional"))
    )
    (net (code "45") (name "SCK") (class "Default")
      (node (ref "D10") (pin "2") (pinfunction "2_2") (pintype "passive"))
      (node (ref "J1") (pin "13") (pinfunction "13_13") (pintype "bidirectional"))
      (node (ref "J4") (pin "P5") (pinfunction "CLK_P5") (pintype "bidirectional"))
      (node (ref "R6") (pin "1") (pinfunction "1_1") (pintype "passive"))
      (node (ref "TP8") (pin "TP") (pinfunction "TP_TP") (pintype "input"))
      (node (ref "U1") (pin "6") (pinfunction "CLK_6") (pintype "input"))
      (node (ref "U2") (pin "6") (pinfunction "IO6_6") (pintype "bidirectional"))
    )
    (net (code "46") (name "SCL") (class "Default")
      (node (ref "J3") (pin "4") (pinfunction "4_4") (pintype "passive"))
      (node (ref "R2-PINH") (pin "1") (pinfunction "1_1") (pintype "passive"))
      (node (ref "SENSOR2") (pin "4") (pinfunction "SCK_4") (pintype "input"))
      (node (ref "U2") (pin "20") (pinfunction "IO22_20") (pintype "bidirectional"))
      (node (ref "U3") (pin "16") (pinfunction "SCL_16") (pintype "input"))
      (node (ref "U4") (pin "7") (pinfunction "SCL_7") (pintype "input"))
    )
    (net (code "47") (name "SDA") (class "Default")
      (node (ref "J3") (pin "3") (pinfunction "3_3") (pintype "passive"))
      (node (ref "R1-PINH") (pin "1") (pinfunction "1_1") (pintype "passive"))
      (node (ref "SENSOR2") (pin "3") (pinfunction "SDI_3") (pintype "bidirectional"))
      (node (ref "U2") (pin "19") (pinfunction "IO21_19") (pintype "bidirectional"))
      (node (ref "U3") (pin "15") (pinfunction "SDA_15") (pintype "bidirectional"))
      (node (ref "U4") (pin "8") (pinfunction "SDA_8") (pintype "bidirectional"))
    )
    (net (code "48") (name "SRC") (class "Default")
      (node (ref "C4") (pin "2") (pinfunction "2_2") (pintype "passive"))
      (node (ref "D5") (pin "2") (pinfunction "A_2") (pintype "bidirectional"))
      (node (ref "L1") (pin "1") (pinfunction "1_1") (pintype "passive"))
      (node (ref "Q3") (pin "3") (pinfunction "D_3") (pintype "bidirectional"))
    )
    (net (code "49") (name "SS_SD") (class "Default")
      (node (ref "D8") (pin "2") (pinfunction "2_2") (pintype "passive"))
      (node (ref "J4") (pin "P2") (pinfunction "CD/DAT3_P2") (pintype "bidirectional"))
      (node (ref "R10") (pin "1") (pinfunction "1_1") (pintype "passive"))
      (node (ref "U2") (pin "4") (pinfunction "IO4_4") (pintype "bidirectional"))
    )
    (net (code "50") (name "TX") (class "Default")
      (node (ref "TP1") (pin "TP") (pinfunction "TP_TP") (pintype "input"))
      (node (ref "U2") (pin "25") (pinfunction "TXD0/GPIO16_25") (pintype "bidirectional"))
    )
    (net (code "51") (name "USB_D+") (class "Default")
      (node (ref "D1") (pin "4") (pinfunction "I/O2_2_4") (pintype "bidirectional"))
      (node (ref "U2") (pin "14") (pinfunction "IO13_14") (pintype "bidirectional"))
    )
    (net (code "52") (name "USB_D-") (class "Default")
      (node (ref "D1") (pin "6") (pinfunction "I/O1_2_6") (pintype "bidirectional"))
      (node (ref "U2") (pin "13") (pinfunction "IO12_13") (pintype "bidirectional"))
    )
    (net (code "53") (name "VBAT") (class "Default")
      (node (ref "C2_BAT") (pin "1") (pinfunction "1_1") (pintype "passive"))
      (node (ref "Q1") (pin "3") (pinfunction "D_3") (pintype "bidirectional"))
      (node (ref "TP3") (pin "TP") (pinfunction "TP_TP") (pintype "input"))
      (node (ref "U4") (pin "2") (pinfunction "CELL_2") (pintype "power_in"))
      (node (ref "U4") (pin "3") (pinfunction "VDD_3") (pintype "power_in"))
      (node (ref "U5") (pin "3") (pinfunction "VBAT_3") (pintype "power_in"))
    )
    (net (code "54") (name "VBUS") (class "Default")
      (node (ref "C1_BAT") (pin "1") (pinfunction "1_1") (pintype "passive"))
      (node (ref "C4_USB") (pin "1") (pinfunction "1_1") (pintype "passive"))
      (node (ref "C5_USB") (pin "1") (pinfunction "1_1") (pintype "passive"))
      (node (ref "CHG_LED") (pin "A") (pinfunction "A_A") (pintype "passive"))
      (node (ref "D1") (pin "2") (pinfunction "GND_2") (pintype "bidirectional"))
      (node (ref "D2") (pin "2") (pinfunction "ANODE_2") (pintype "bidirectional"))
      (node (ref "PFMF.050.1") (pin "2") (pinfunction "2_2") (pintype "passive"))
      (node (ref "Q1") (pin "1") (pinfunction "G_1") (pintype "bidirectional"))
      (node (ref "R1_PWRUSB") (pin "2") (pinfunction "2_2") (pintype "passive"))
      (node (ref "TP14") (pin "TP") (pinfunction "TP_TP") (pintype "input"))
      (node (ref "U5") (pin "4") (pinfunction "VIN_4") (pintype "power_in"))
    )
    (net (code "55") (name "VRTC") (class "Default")
      (node (ref "C10_SUPERCAP") (pin "1") (pinfunction "1_1") (pintype "passive"))
      (node (ref "C8") (pin "1") (pinfunction "1_1") (pintype "passive"))
      (node (ref "R_CAPACITOR") (pin "2") (pinfunction "2_2") (pintype "passive"))
      (node (ref "U3") (pin "14") (pinfunction "VBAT_14") (pintype "power_in"))
    )
    (net (code "56") (name "VUSB") (class "Default")
      (node (ref "J2") (pin "A4") (pinfunction "A4_A4") (pintype "bidirectional"))
      (node (ref "J2") (pin "A9") (pinfunction "A9_A9") (pintype "bidirectional"))
      (node (ref "J2") (pin "B4") (pinfunction "B4_B4") (pintype "bidirectional"))
      (node (ref "J2") (pin "B9") (pinfunction "B9_B9") (pintype "bidirectional"))
      (node (ref "PFMF.050.1") (pin "1") (pinfunction "1_1") (pintype "passive"))
    )
    (net (code "57") (name "unconnected-(IC1-NC-Pad4)") (class "Default")
      (node (ref "IC1") (pin "4") (pinfunction "NC_4") (pintype "no_connect"))
    )
    (net (code "58") (name "unconnected-(IC4-NC-Pad4)") (class "Default")
      (node (ref "IC4") (pin "4") (pinfunction "NC_4") (pintype "no_connect"))
    )
    (net (code "59") (name "unconnected-(J1-Pad1)") (class "Default")
      (node (ref "J1") (pin "1") (pinfunction "1_1") (pintype "bidirectional"))
    )
    (net (code "60") (name "unconnected-(J1-Pad6)") (class "Default")
      (node (ref "J1") (pin "6") (pinfunction "6_6") (pintype "bidirectional"))
    )
    (net (code "61") (name "unconnected-(J1-Pad7)") (class "Default")
      (node (ref "J1") (pin "7") (pinfunction "7_7") (pintype "bidirectional"))
    )
    (net (code "62") (name "unconnected-(J2-PadA8)") (class "Default")
      (node (ref "J2") (pin "A8") (pinfunction "A8_A8") (pintype "bidirectional"))
    )
    (net (code "63") (name "unconnected-(J2-PadB8)") (class "Default")
      (node (ref "J2") (pin "B8") (pinfunction "B8_B8") (pintype "bidirectional"))
    )
    (net (code "64") (name "unconnected-(J4-DAT1-PadP8)") (class "Default")
      (node (ref "J4") (pin "P8") (pinfunction "DAT1_P8") (pintype "bidirectional"))
    )
    (net (code "65") (name "unconnected-(J4-DAT2-PadP1)") (class "Default")
      (node (ref "J4") (pin "P1") (pinfunction "DAT2_P1") (pintype "bidirectional"))
    )
    (net (code "66") (name "unconnected-(J4-DETECTION_1-PadS1)") (class "Default")
      (node (ref "J4") (pin "S1") (pinfunction "DETECTION_1_S1") (pintype "bidirectional"))
    )
    (net (code "67") (name "unconnected-(J4-DETECTION_2-PadS2)") (class "Default")
      (node (ref "J4") (pin "S2") (pinfunction "DETECTION_2_S2") (pintype "bidirectional"))
    )
    (net (code "68") (name "unconnected-(U2-NC-Pad22)") (class "Default")
      (node (ref "U2") (pin "22") (pinfunction "NC_22") (pintype "no_connect"))
    )
    (net (code "69") (name "unconnected-(U4-~{ALERT}-Pad5)") (class "Default")
      (node (ref "U4") (pin "5") (pinfunction "~{ALERT}_5") (pintype "output"))
    )
  )
)
